# PA_PShifter_R01.net
KiCad netlist of a schematic drawn in Altium Designer
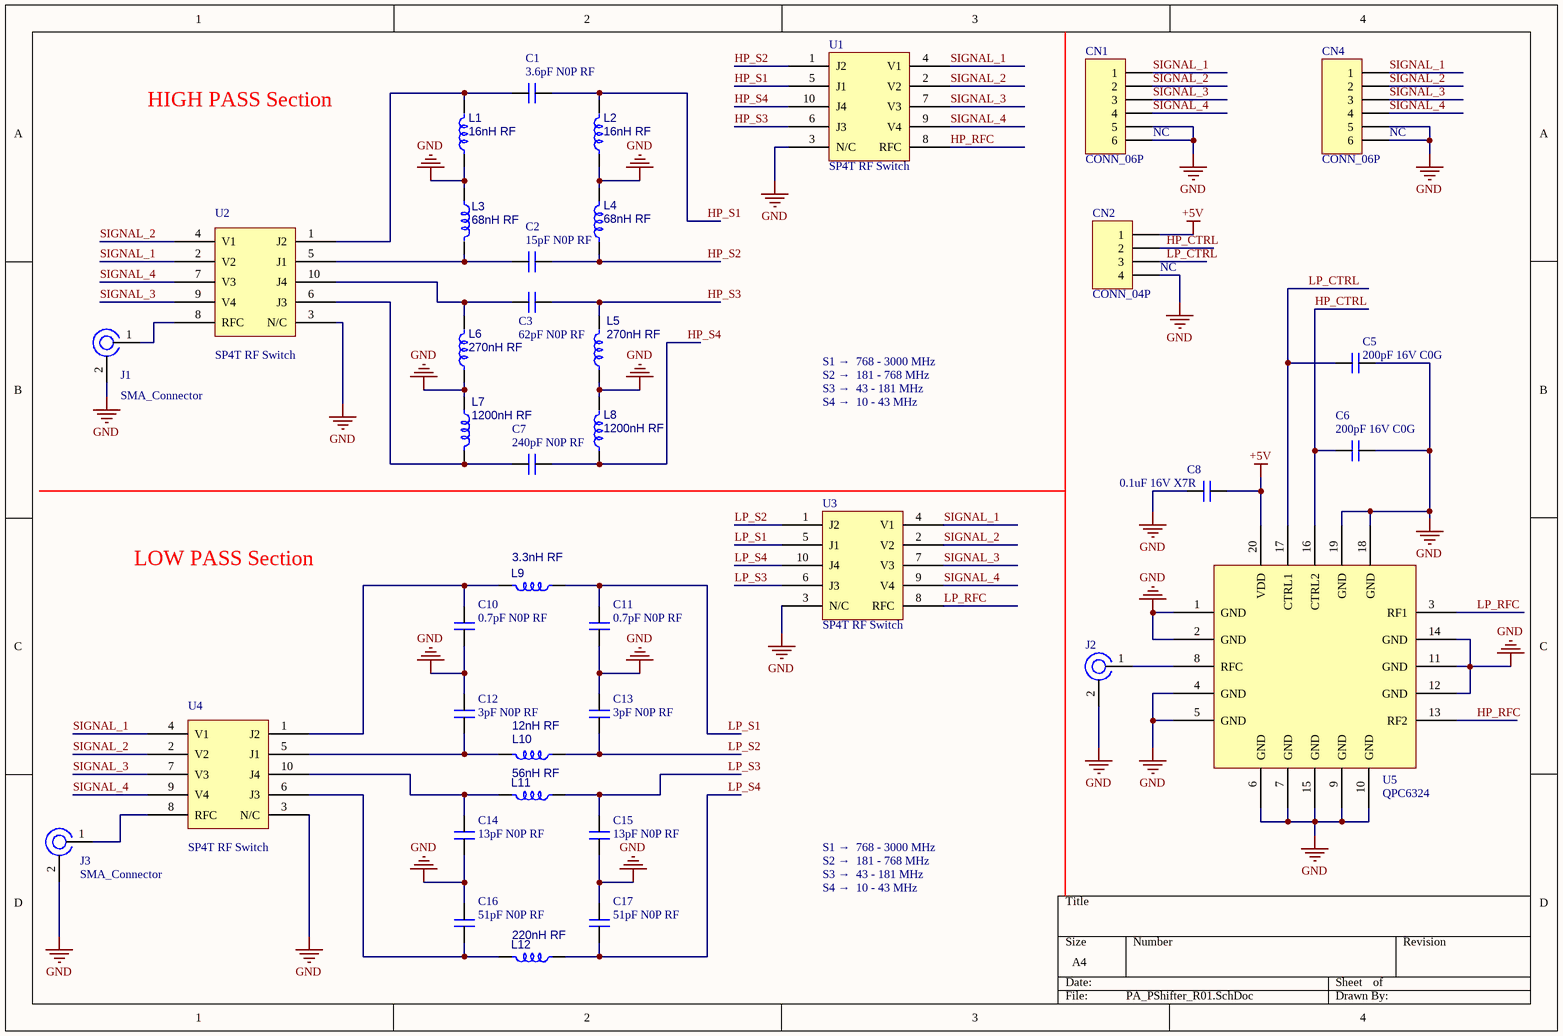
[diagram p0: PA_PShifter_R01.SchDoc]

(export (version "E")
  (design (tool "Eeschema 10.0.6"))
  (components
    (comp (ref "C1")
      (value "3.6pF N0P RF")
      (footprint "C_0603")
      (libsource (lib "SchLib_PocketAnalyzer") (part "Ceramic Cap"))
    )
    (comp (ref "C2")
      (value "15pF N0P RF")
      (footprint "C_0603")
      (libsource (lib "SchLib_PocketAnalyzer") (part "Ceramic Cap"))
    )
    (comp (ref "C3")
      (value "62pF N0P RF")
      (footprint "C_0603")
      (libsource (lib "SchLib_PocketAnalyzer") (part "Ceramic Cap"))
    )
    (comp (ref "C5")
      (value "200pF 16V C0G")
      (footprint "C_0603")
      (libsource (lib "SchLib_MPPT") (part "Ceramic Cap"))
    )
    (comp (ref "C6")
      (value "200pF 16V C0G")
      (footprint "C_0603")
      (libsource (lib "SchLib_MPPT") (part "Ceramic Cap"))
    )
    (comp (ref "C7")
      (value "240pF N0P RF")
      (footprint "C_0603")
      (libsource (lib "SchLib_PocketAnalyzer") (part "Ceramic Cap"))
    )
    (comp (ref "C8")
      (value "0.1uF 16V X7R")
      (footprint "C_0603")
      (libsource (lib "SchLib_MPPT") (part "Ceramic Cap"))
    )
    (comp (ref "C10")
      (value "0.7pF N0P RF")
      (footprint "C_0603")
      (libsource (lib "SchLib_PocketAnalyzer") (part "Ceramic Cap"))
    )
    (comp (ref "C11")
      (value "0.7pF N0P RF")
      (footprint "C_0603")
      (libsource (lib "SchLib_PocketAnalyzer") (part "Ceramic Cap"))
    )
    (comp (ref "C12")
      (value "3pF N0P RF")
      (footprint "C_0603")
      (libsource (lib "SchLib_PocketAnalyzer") (part "Ceramic Cap"))
    )
    (comp (ref "C13")
      (value "3pF N0P RF")
      (footprint "C_0603")
      (libsource (lib "SchLib_PocketAnalyzer") (part "Ceramic Cap"))
    )
    (comp (ref "C14")
      (value "13pF N0P RF")
      (footprint "C_0603")
      (libsource (lib "SchLib_PocketAnalyzer") (part "Ceramic Cap"))
    )
    (comp (ref "C15")
      (value "13pF N0P RF")
      (footprint "C_0603")
      (libsource (lib "SchLib_PocketAnalyzer") (part "Ceramic Cap"))
    )
    (comp (ref "C16")
      (value "51pF N0P RF")
      (footprint "C_0603")
      (libsource (lib "SchLib_PocketAnalyzer") (part "Ceramic Cap"))
    )
    (comp (ref "C17")
      (value "51pF N0P RF")
      (footprint "C_0603")
      (libsource (lib "SchLib_PocketAnalyzer") (part "Ceramic Cap"))
    )
    (comp (ref "CN1")
      (value "CONN_06P")
      (footprint "Header_M_2x3_0.1\"")
      (description "Connector Generic 4 Vias")
      (libsource (lib "SchLib_PocketAnalyzer") (part "CONN_06P"))
    )
    (comp (ref "CN2")
      (value "CONN_04P")
      (footprint "Header_M_2x2_0.1\"")
      (description "Connector Generic 4 Vias")
      (libsource (lib "SchLib_PocketAnalyzer") (part "CONN_04P"))
    )
    (comp (ref "CN4")
      (value "CONN_06P")
      (footprint "Header_M_2x3_0.1\"")
      (description "Connector Generic 4 Vias")
      (libsource (lib "SchLib_PocketAnalyzer") (part "CONN_06P"))
    )
    (comp (ref "J1")
      (value "SMA_Connector")
      (footprint "SMA_Connector")
      (description "Connector SMA")
      (libsource (lib "SchLib_PocketAnalyzer") (part "SMA_Connector"))
    )
    (comp (ref "J2")
      (value "SMA_Connector")
      (footprint "SMA_Connector")
      (description "Connector SMA")
      (libsource (lib "SchLib_MPPT") (part "SMA_Connector"))
    )
    (comp (ref "J3")
      (value "SMA_Connector")
      (footprint "SMA_Connector")
      (description "Connector SMA")
      (libsource (lib "SchLib_PocketAnalyzer") (part "SMA_Connector"))
    )
    (comp (ref "L1")
      (value "16nH RF")
      (footprint "L_0603")
      (description "CHIP inductor")
      (libsource (lib "SchLib_PocketAnalyzer") (part "Inductor Chip"))
    )
    (comp (ref "L2")
      (value "16nH RF")
      (footprint "L_0603")
      (description "CHIP inductor")
      (libsource (lib "SchLib_PocketAnalyzer") (part "Inductor Chip"))
    )
    (comp (ref "L3")
      (value "68nH RF")
      (footprint "L_0603")
      (description "CHIP inductor")
      (libsource (lib "SchLib_PocketAnalyzer") (part "Inductor Chip"))
    )
    (comp (ref "L4")
      (value "68nH RF")
      (footprint "L_0603")
      (description "CHIP inductor")
      (libsource (lib "SchLib_PocketAnalyzer") (part "Inductor Chip"))
    )
    (comp (ref "L5")
      (value "270nH RF")
      (footprint "L_0603")
      (description "CHIP inductor")
      (libsource (lib "SchLib_PocketAnalyzer") (part "Inductor Chip"))
    )
    (comp (ref "L6")
      (value "270nH RF")
      (footprint "L_0603")
      (description "CHIP inductor")
      (libsource (lib "SchLib_PocketAnalyzer") (part "Inductor Chip"))
    )
    (comp (ref "L7")
      (value "1200nH RF")
      (footprint "L_0805")
      (description "CHIP inductor")
      (libsource (lib "SchLib_PocketAnalyzer") (part "Inductor Chip"))
    )
    (comp (ref "L8")
      (value "1200nH RF")
      (footprint "L_0805")
      (description "CHIP inductor")
      (libsource (lib "SchLib_PocketAnalyzer") (part "Inductor Chip"))
    )
    (comp (ref "L9")
      (value "3.3nH RF")
      (footprint "L_0603")
      (description "CHIP inductor")
      (libsource (lib "SchLib_PocketAnalyzer") (part "Inductor Chip"))
    )
    (comp (ref "L10")
      (value "12nH RF")
      (footprint "L_0603")
      (description "CHIP inductor")
      (libsource (lib "SchLib_PocketAnalyzer") (part "Inductor Chip"))
    )
    (comp (ref "L11")
      (value "56nH RF")
      (footprint "L_0603")
      (description "CHIP inductor")
      (libsource (lib "SchLib_PocketAnalyzer") (part "Inductor Chip"))
    )
    (comp (ref "L12")
      (value "220nH RF")
      (footprint "L_0603")
      (description "CHIP inductor")
      (libsource (lib "SchLib_PocketAnalyzer") (part "Inductor Chip"))
    )
    (comp (ref "U1")
      (value "SP4T RF Switch")
      (footprint "SP4T Switch RF")
      (description "SKY13322-375LF")
      (libsource (lib "SchLib_PocketAnalyzer") (part "SP4T RF Switch"))
    )
    (comp (ref "U2")
      (value "SP4T RF Switch")
      (footprint "SP4T Switch RF")
      (description "SKY13322-375LF")
      (libsource (lib "") (part "SP4T RF Switch_1"))
    )
    (comp (ref "U3")
      (value "SP4T RF Switch")
      (footprint "SP4T Switch RF")
      (description "SKY13322-375LF")
      (libsource (lib "SchLib_PocketAnalyzer") (part "SP4T RF Switch"))
    )
    (comp (ref "U4")
      (value "SP4T RF Switch")
      (footprint "SP4T Switch RF")
      (description "SKY13322-375LF")
      (libsource (lib "") (part "SP4T RF Switch_1"))
    )
    (comp (ref "U5")
      (value "QPC6324")
      (footprint "QFN50P400X400X90-21N-D")
      (description "SPDT RF Switch")
      (libsource (lib "SchLib_MPPT") (part "QPC6324"))
    )
  )
  (nets
    (net (code "1") (name "+5V") (class "Default")
      (node (ref "C8") (pin "2") (pintype "passive"))
      (node (ref "CN2") (pin "1") (pinfunction "1_1") (pintype "passive"))
      (node (ref "U5") (pin "20") (pinfunction "VDD_20") (pintype "passive"))
    )
    (net (code "2") (name "/HP_CTRL") (class "Default")
      (node (ref "C6") (pin "1") (pintype "passive"))
      (node (ref "CN2") (pin "2") (pinfunction "2_2") (pintype "passive"))
      (node (ref "U5") (pin "16") (pinfunction "CTRL2_16") (pintype "passive"))
    )
    (net (code "3") (name "/HP_RFC") (class "Default")
      (node (ref "U1") (pin "8") (pinfunction "RFC_8") (pintype "passive"))
      (node (ref "U5") (pin "13") (pinfunction "RF2_13") (pintype "passive"))
    )
    (net (code "4") (name "/HP_S1") (class "Default")
      (node (ref "C1") (pin "2") (pintype "passive"))
      (node (ref "L2") (pin "2") (pinfunction "2_2") (pintype "passive"))
      (node (ref "U1") (pin "5") (pinfunction "J1_5") (pintype "passive"))
    )
    (net (code "5") (name "/HP_S2") (class "Default")
      (node (ref "C2") (pin "2") (pintype "passive"))
      (node (ref "L4") (pin "1") (pinfunction "1_1") (pintype "passive"))
      (node (ref "U1") (pin "1") (pinfunction "J2_1") (pintype "passive"))
    )
    (net (code "6") (name "/HP_S3") (class "Default")
      (node (ref "C3") (pin "2") (pintype "passive"))
      (node (ref "L5") (pin "2") (pinfunction "2_2") (pintype "passive"))
      (node (ref "U1") (pin "6") (pinfunction "J3_6") (pintype "passive"))
    )
    (net (code "7") (name "/HP_S4") (class "Default")
      (node (ref "C7") (pin "2") (pintype "passive"))
      (node (ref "L8") (pin "1") (pinfunction "1_1") (pintype "passive"))
      (node (ref "U1") (pin "10") (pinfunction "J4_10") (pintype "passive"))
    )
    (net (code "8") (name "/LP_CTRL") (class "Default")
      (node (ref "C5") (pin "1") (pintype "passive"))
      (node (ref "CN2") (pin "3") (pinfunction "3_3") (pintype "passive"))
      (node (ref "U5") (pin "17") (pinfunction "CTRL1_17") (pintype "passive"))
    )
    (net (code "9") (name "/LP_RFC") (class "Default")
      (node (ref "U3") (pin "8") (pinfunction "RFC_8") (pintype "passive"))
      (node (ref "U5") (pin "3") (pinfunction "RF1_3") (pintype "passive"))
    )
    (net (code "10") (name "/LP_S1") (class "Default")
      (node (ref "C11") (pin "2") (pintype "passive"))
      (node (ref "L9") (pin "1") (pinfunction "1_1") (pintype "passive"))
      (node (ref "U3") (pin "5") (pinfunction "J1_5") (pintype "passive"))
    )
    (net (code "11") (name "/LP_S2") (class "Default")
      (node (ref "C13") (pin "1") (pintype "passive"))
      (node (ref "L10") (pin "1") (pinfunction "1_1") (pintype "passive"))
      (node (ref "U3") (pin "1") (pinfunction "J2_1") (pintype "passive"))
    )
    (net (code "12") (name "/LP_S3") (class "Default")
      (node (ref "C15") (pin "2") (pintype "passive"))
      (node (ref "L11") (pin "1") (pinfunction "1_1") (pintype "passive"))
      (node (ref "U3") (pin "6") (pinfunction "J3_6") (pintype "passive"))
    )
    (net (code "13") (name "/LP_S4") (class "Default")
      (node (ref "C17") (pin "1") (pintype "passive"))
      (node (ref "L12") (pin "1") (pinfunction "1_1") (pintype "passive"))
      (node (ref "U3") (pin "10") (pinfunction "J4_10") (pintype "passive"))
    )
    (net (code "14") (name "/SIGNAL_1") (class "Default")
      (node (ref "CN1") (pin "1") (pinfunction "1_1") (pintype "passive"))
      (node (ref "CN4") (pin "1") (pinfunction "1_1") (pintype "passive"))
      (node (ref "U1") (pin "4") (pinfunction "V1_4") (pintype "passive"))
      (node (ref "U2") (pin "2") (pinfunction "V2_2") (pintype "passive"))
      (node (ref "U3") (pin "4") (pinfunction "V1_4") (pintype "passive"))
      (node (ref "U4") (pin "4") (pinfunction "V1_4") (pintype "passive"))
    )
    (net (code "15") (name "/SIGNAL_2") (class "Default")
      (node (ref "CN1") (pin "2") (pinfunction "2_2") (pintype "passive"))
      (node (ref "CN4") (pin "2") (pinfunction "2_2") (pintype "passive"))
      (node (ref "U1") (pin "2") (pinfunction "V2_2") (pintype "passive"))
      (node (ref "U2") (pin "4") (pinfunction "V1_4") (pintype "passive"))
      (node (ref "U3") (pin "2") (pinfunction "V2_2") (pintype "passive"))
      (node (ref "U4") (pin "2") (pinfunction "V2_2") (pintype "passive"))
    )
    (net (code "16") (name "/SIGNAL_3") (class "Default")
      (node (ref "CN1") (pin "3") (pinfunction "3_3") (pintype "passive"))
      (node (ref "CN4") (pin "3") (pinfunction "3_3") (pintype "passive"))
      (node (ref "U1") (pin "7") (pinfunction "V3_7") (pintype "passive"))
      (node (ref "U2") (pin "9") (pinfunction "V4_9") (pintype "passive"))
      (node (ref "U3") (pin "7") (pinfunction "V3_7") (pintype "passive"))
      (node (ref "U4") (pin "7") (pinfunction "V3_7") (pintype "passive"))
    )
    (net (code "17") (name "/SIGNAL_4") (class "Default")
      (node (ref "CN1") (pin "4") (pinfunction "4_4") (pintype "passive"))
      (node (ref "CN4") (pin "4") (pinfunction "4_4") (pintype "passive"))
      (node (ref "U1") (pin "9") (pinfunction "V4_9") (pintype "passive"))
      (node (ref "U2") (pin "7") (pinfunction "V3_7") (pintype "passive"))
      (node (ref "U3") (pin "9") (pinfunction "V4_9") (pintype "passive"))
      (node (ref "U4") (pin "9") (pinfunction "V4_9") (pintype "passive"))
    )
    (net (code "18") (name "GND") (class "Default")
      (node (ref "C10") (pin "1") (pintype "passive"))
      (node (ref "C11") (pin "1") (pintype "passive"))
      (node (ref "C12") (pin "2") (pintype "passive"))
      (node (ref "C13") (pin "2") (pintype "passive"))
      (node (ref "C14") (pin "1") (pintype "passive"))
      (node (ref "C15") (pin "1") (pintype "passive"))
      (node (ref "C16") (pin "2") (pintype "passive"))
      (node (ref "C17") (pin "2") (pintype "passive"))
      (node (ref "C5") (pin "2") (pintype "passive"))
      (node (ref "C6") (pin "2") (pintype "passive"))
      (node (ref "C8") (pin "1") (pintype "passive"))
      (node (ref "CN1") (pin "5") (pinfunction "5_5") (pintype "passive"))
      (node (ref "CN1") (pin "6") (pinfunction "6_6") (pintype "passive"))
      (node (ref "CN2") (pin "4") (pinfunction "4_4") (pintype "passive"))
      (node (ref "CN4") (pin "5") (pinfunction "5_5") (pintype "passive"))
      (node (ref "CN4") (pin "6") (pinfunction "6_6") (pintype "passive"))
      (node (ref "J1") (pin "2") (pinfunction "2_2") (pintype "passive"))
      (node (ref "J2") (pin "2") (pinfunction "2_2") (pintype "passive"))
      (node (ref "J3") (pin "2") (pinfunction "2_2") (pintype "passive"))
      (node (ref "L1") (pin "1") (pinfunction "1_1") (pintype "passive"))
      (node (ref "L2") (pin "1") (pinfunction "1_1") (pintype "passive"))
      (node (ref "L3") (pin "1") (pinfunction "1_1") (pintype "passive"))
      (node (ref "L4") (pin "2") (pinfunction "2_2") (pintype "passive"))
      (node (ref "L5") (pin "1") (pinfunction "1_1") (pintype "passive"))
      (node (ref "L6") (pin "1") (pinfunction "1_1") (pintype "passive"))
      (node (ref "L7") (pin "1") (pinfunction "1_1") (pintype "passive"))
      (node (ref "L8") (pin "2") (pinfunction "2_2") (pintype "passive"))
      (node (ref "U1") (pin "3") (pinfunction "N/C_3") (pintype "passive"))
      (node (ref "U2") (pin "3") (pinfunction "N/C_3") (pintype "passive"))
      (node (ref "U3") (pin "3") (pinfunction "N/C_3") (pintype "passive"))
      (node (ref "U4") (pin "3") (pinfunction "N/C_3") (pintype "passive"))
      (node (ref "U5") (pin "1") (pinfunction "GND_1") (pintype "passive"))
      (node (ref "U5") (pin "10") (pinfunction "GND_10") (pintype "passive"))
      (node (ref "U5") (pin "11") (pinfunction "GND_11") (pintype "passive"))
      (node (ref "U5") (pin "12") (pinfunction "GND_12") (pintype "passive"))
      (node (ref "U5") (pin "14") (pinfunction "GND_14") (pintype "passive"))
      (node (ref "U5") (pin "15") (pinfunction "GND_15") (pintype "passive"))
      (node (ref "U5") (pin "18") (pinfunction "GND_18") (pintype "passive"))
      (node (ref "U5") (pin "19") (pinfunction "GND_19") (pintype "passive"))
      (node (ref "U5") (pin "2") (pinfunction "GND_2") (pintype "passive"))
      (node (ref "U5") (pin "4") (pinfunction "GND_4") (pintype "passive"))
      (node (ref "U5") (pin "5") (pinfunction "GND_5") (pintype "passive"))
      (node (ref "U5") (pin "6") (pinfunction "GND_6") (pintype "passive"))
      (node (ref "U5") (pin "7") (pinfunction "GND_7") (pintype "passive"))
      (node (ref "U5") (pin "9") (pinfunction "GND_9") (pintype "passive"))
    )
    (net (code "19") (name "Net-(U2-J1)") (class "Default")
      (node (ref "C2") (pin "1") (pintype "passive"))
      (node (ref "L3") (pin "2") (pinfunction "2_2") (pintype "passive"))
      (node (ref "U2") (pin "5") (pinfunction "J1_5") (pintype "passive"))
    )
    (net (code "20") (name "Net-(U2-J2)") (class "Default")
      (node (ref "C1") (pin "1") (pintype "passive"))
      (node (ref "L1") (pin "2") (pinfunction "2_2") (pintype "passive"))
      (node (ref "U2") (pin "1") (pinfunction "J2_1") (pintype "passive"))
    )
    (net (code "21") (name "Net-(U2-J3)") (class "Default")
      (node (ref "C7") (pin "1") (pintype "passive"))
      (node (ref "L7") (pin "2") (pinfunction "2_2") (pintype "passive"))
      (node (ref "U2") (pin "6") (pinfunction "J3_6") (pintype "passive"))
    )
    (net (code "22") (name "Net-(U2-J4)") (class "Default")
      (node (ref "C3") (pin "1") (pintype "passive"))
      (node (ref "L6") (pin "2") (pinfunction "2_2") (pintype "passive"))
      (node (ref "U2") (pin "10") (pinfunction "J4_10") (pintype "passive"))
    )
    (net (code "23") (name "Net-(U2-RFC)") (class "Default")
      (node (ref "J1") (pin "1") (pinfunction "1_1") (pintype "passive"))
      (node (ref "U2") (pin "8") (pinfunction "RFC_8") (pintype "passive"))
    )
    (net (code "24") (name "Net-(U4-J1)") (class "Default")
      (node (ref "C12") (pin "1") (pintype "passive"))
      (node (ref "L10") (pin "2") (pinfunction "2_2") (pintype "passive"))
      (node (ref "U4") (pin "5") (pinfunction "J1_5") (pintype "passive"))
    )
    (net (code "25") (name "Net-(U4-J2)") (class "Default")
      (node (ref "C10") (pin "2") (pintype "passive"))
      (node (ref "L9") (pin "2") (pinfunction "2_2") (pintype "passive"))
      (node (ref "U4") (pin "1") (pinfunction "J2_1") (pintype "passive"))
    )
    (net (code "26") (name "Net-(U4-J3)") (class "Default")
      (node (ref "C16") (pin "1") (pintype "passive"))
      (node (ref "L12") (pin "2") (pinfunction "2_2") (pintype "passive"))
      (node (ref "U4") (pin "6") (pinfunction "J3_6") (pintype "passive"))
    )
    (net (code "27") (name "Net-(U4-J4)") (class "Default")
      (node (ref "C14") (pin "2") (pintype "passive"))
      (node (ref "L11") (pin "2") (pinfunction "2_2") (pintype "passive"))
      (node (ref "U4") (pin "10") (pinfunction "J4_10") (pintype "passive"))
    )
    (net (code "28") (name "Net-(U4-RFC)") (class "Default")
      (node (ref "J3") (pin "1") (pinfunction "1_1") (pintype "passive"))
      (node (ref "U4") (pin "8") (pinfunction "RFC_8") (pintype "passive"))
    )
    (net (code "29") (name "Net-(U5-RFC)") (class "Default")
      (node (ref "J2") (pin "1") (pinfunction "1_1") (pintype "passive"))
      (node (ref "U5") (pin "8") (pinfunction "RFC_8") (pintype "passive"))
    )
  )
)
